# Sheet_relay.net
KiCad netlist of a schematic drawn in Altium Designer
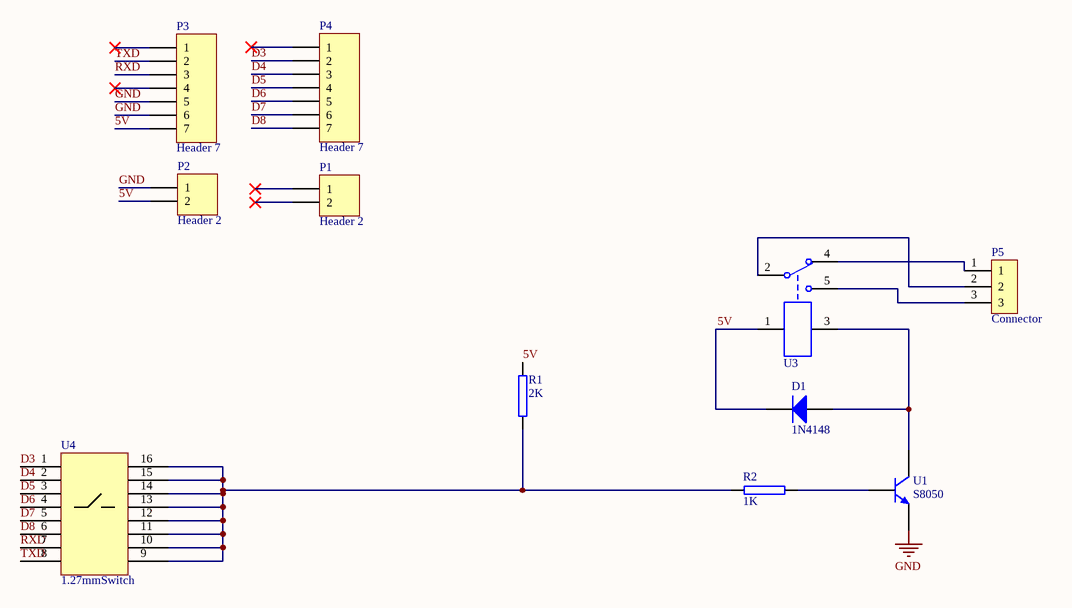
[diagram p0: Sheet_relay.SchDoc]

(export (version "E")
  (design (tool "Eeschema 10.0.6"))
  (components
    (comp (ref "D1")
      (value "1N4148")
      (footprint "1n4148")
      (description "二极管")
      (libsource (lib "Schlib_OLEDMCU") (part "1N4148"))
    )
    (comp (ref "P1")
      (value "Header 2")
      (footprint "HDR1X2")
      (description "Header, 2-Pin")
      (fields (field (name "PUBLISHER") "Altium Limited"))
      (libsource (lib "Miscellaneous Connectors") (part "Header 2"))
    )
    (comp (ref "P2")
      (value "Header 2")
      (footprint "HDR1X2")
      (description "Header, 2-Pin")
      (fields (field (name "PUBLISHER") "Altium Limited"))
      (libsource (lib "Miscellaneous Connectors") (part "Header 2"))
    )
    (comp (ref "P3")
      (value "Header 7")
      (footprint "HDR1X7")
      (description "Header, 7-Pin")
      (fields (field (name "PUBLISHER") "Altium Limited"))
      (libsource (lib "Miscellaneous Connectors") (part "Header 7"))
    )
    (comp (ref "P4")
      (value "Header 7")
      (footprint "HDR1X7")
      (description "Header, 7-Pin")
      (fields (field (name "PUBLISHER") "Altium Limited"))
      (libsource (lib "Miscellaneous Connectors") (part "Header 7"))
    )
    (comp (ref "P5")
      (value "Connector")
      (footprint "3p")
      (description "3P端子5mm")
      (libsource (lib "Schlib_OLEDMCU") (part "3P"))
    )
    (comp (ref "R1")
      (value "2K")
      (footprint "R0603")
      (description "贴片电阻")
      (libsource (lib "Schlib_OLEDMCU") (part "R0603"))
    )
    (comp (ref "R2")
      (value "1K")
      (footprint "R0603")
      (description "贴片电阻")
      (libsource (lib "Schlib_OLEDMCU") (part "R0603"))
    )
    (comp (ref "U1")
      (value "S8050")
      (footprint "s8050")
      (description "三极管")
      (libsource (lib "Schlib_OLEDMCU") (part "S8050"))
    )
    (comp (ref "U3")
      (value "SRD-05VDC-SL-C")
      (footprint "Relay")
      (description "继电器")
      (libsource (lib "Schlib_OLEDMCU") (part "Relay"))
    )
    (comp (ref "U4")
      (value "1.27mmSwitch")
      (footprint "NumberSwitch")
      (description "拨码开关")
      (libsource (lib "Schlib_OLEDMCU") (part "NumberSwitch"))
    )
  )
  (nets
    (net (code "1") (name "/5V") (class "Default")
      (node (ref "D1") (pin "2") (pinfunction "K_2") (pintype "passive"))
      (node (ref "P2") (pin "2") (pinfunction "2_2") (pintype "passive"))
      (node (ref "P3") (pin "7") (pinfunction "7_7") (pintype "passive"))
      (node (ref "R1") (pin "2") (pinfunction "2_2") (pintype "passive"))
      (node (ref "U3") (pin "1") (pinfunction "1_1") (pintype "passive"))
    )
    (net (code "2") (name "/D3") (class "Default")
      (node (ref "P4") (pin "2") (pinfunction "2_2") (pintype "passive"))
      (node (ref "U4") (pin "1") (pinfunction "1_1") (pintype "passive"))
    )
    (net (code "3") (name "/D4") (class "Default")
      (node (ref "P4") (pin "3") (pinfunction "3_3") (pintype "passive"))
      (node (ref "U4") (pin "2") (pinfunction "2_2") (pintype "passive"))
    )
    (net (code "4") (name "/D5") (class "Default")
      (node (ref "P4") (pin "4") (pinfunction "4_4") (pintype "passive"))
      (node (ref "U4") (pin "3") (pinfunction "3_3") (pintype "passive"))
    )
    (net (code "5") (name "/D6") (class "Default")
      (node (ref "P4") (pin "5") (pinfunction "5_5") (pintype "passive"))
      (node (ref "U4") (pin "4") (pinfunction "4_4") (pintype "passive"))
    )
    (net (code "6") (name "/D7") (class "Default")
      (node (ref "P4") (pin "6") (pinfunction "6_6") (pintype "passive"))
      (node (ref "U4") (pin "5") (pinfunction "5_5") (pintype "passive"))
    )
    (net (code "7") (name "/D8") (class "Default")
      (node (ref "P4") (pin "7") (pinfunction "7_7") (pintype "passive"))
      (node (ref "U4") (pin "6") (pinfunction "6_6") (pintype "passive"))
    )
    (net (code "8") (name "/RXD") (class "Default")
      (node (ref "P3") (pin "3") (pinfunction "3_3") (pintype "passive"))
      (node (ref "U4") (pin "7") (pinfunction "7_7") (pintype "passive"))
    )
    (net (code "9") (name "/TXD") (class "Default")
      (node (ref "P3") (pin "2") (pinfunction "2_2") (pintype "passive"))
      (node (ref "U4") (pin "8") (pinfunction "8_8") (pintype "passive"))
    )
    (net (code "10") (name "GND") (class "Default")
      (node (ref "P2") (pin "1") (pinfunction "1_1") (pintype "passive"))
      (node (ref "P3") (pin "5") (pinfunction "5_5") (pintype "passive"))
      (node (ref "P3") (pin "6") (pinfunction "6_6") (pintype "passive"))
      (node (ref "U1") (pin "2") (pinfunction "E_2") (pintype "passive"))
    )
    (net (code "11") (name "Net-(D1-A)") (class "Default")
      (node (ref "D1") (pin "1") (pinfunction "A_1") (pintype "passive"))
      (node (ref "U1") (pin "3") (pinfunction "C_3") (pintype "passive"))
      (node (ref "U3") (pin "3") (pinfunction "3_3") (pintype "passive"))
    )
    (net (code "12") (name "Net-(P5-Pad1)") (class "Default")
      (node (ref "P5") (pin "1") (pinfunction "1_1") (pintype "passive"))
      (node (ref "U3") (pin "4") (pinfunction "4_4") (pintype "passive"))
    )
    (net (code "13") (name "Net-(P5-Pad2)") (class "Default")
      (node (ref "P5") (pin "2") (pinfunction "2_2") (pintype "passive"))
      (node (ref "U3") (pin "2") (pinfunction "2_2") (pintype "passive"))
    )
    (net (code "14") (name "Net-(P5-Pad3)") (class "Default")
      (node (ref "P5") (pin "3") (pinfunction "3_3") (pintype "passive"))
      (node (ref "U3") (pin "5") (pinfunction "5_5") (pintype "passive"))
    )
    (net (code "15") (name "Net-(R1-Pad1)") (class "Default")
      (node (ref "R1") (pin "1") (pinfunction "1_1") (pintype "passive"))
      (node (ref "R2") (pin "1") (pinfunction "1_1") (pintype "passive"))
      (node (ref "U4") (pin "10") (pinfunction "10_10") (pintype "passive"))
      (node (ref "U4") (pin "11") (pinfunction "11_11") (pintype "passive"))
      (node (ref "U4") (pin "12") (pinfunction "12_12") (pintype "passive"))
      (node (ref "U4") (pin "13") (pinfunction "13_13") (pintype "passive"))
      (node (ref "U4") (pin "14") (pinfunction "14_14") (pintype "passive"))
      (node (ref "U4") (pin "15") (pinfunction "15_15") (pintype "passive"))
      (node (ref "U4") (pin "16") (pinfunction "16_16") (pintype "passive"))
      (node (ref "U4") (pin "9") (pinfunction "9_9") (pintype "passive"))
    )
    (net (code "16") (name "Net-(U1-B)") (class "Default")
      (node (ref "R2") (pin "2") (pinfunction "2_2") (pintype "passive"))
      (node (ref "U1") (pin "1") (pinfunction "B_1") (pintype "passive"))
    )
    (net (code "17") (name "unconnected-(P1-Pad1)") (class "Default")
      (node (ref "P1") (pin "1") (pinfunction "1_1") (pintype "passive+no_connect"))
    )
    (net (code "18") (name "unconnected-(P1-Pad2)") (class "Default")
      (node (ref "P1") (pin "2") (pinfunction "2_2") (pintype "passive+no_connect"))
    )
    (net (code "19") (name "unconnected-(P3-Pad1)") (class "Default")
      (node (ref "P3") (pin "1") (pinfunction "1_1") (pintype "passive+no_connect"))
    )
    (net (code "20") (name "unconnected-(P3-Pad4)") (class "Default")
      (node (ref "P3") (pin "4") (pinfunction "4_4") (pintype "passive+no_connect"))
    )
    (net (code "21") (name "unconnected-(P4-Pad1)") (class "Default")
      (node (ref "P4") (pin "1") (pinfunction "1_1") (pintype "passive+no_connect"))
    )
  )
)
